# IndAlarmSe0.net
KiCad netlist of a schematic drawn in Altium Designer
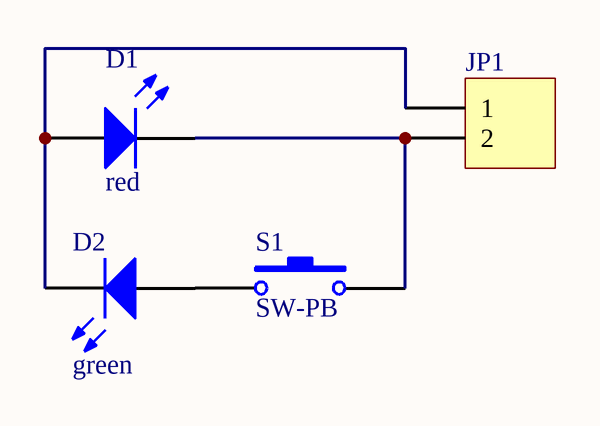
[diagram p0: IndAlarmSe0.SchDoc]

(export (version "E")
  (design (tool "Eeschema 10.0.6"))
  (components
    (comp (ref "D1")
      (value "red")
      (footprint "myLIB:led3mm")
      (description "Typical BLUE SiC LED")
      (fields (field (name "PUBLISHER") "Altium Limited"))
      (libsource (lib "Miscellaneous Devices") (part "LED3"))
    )
    (comp (ref "D2")
      (value "green")
      (footprint "myLIB:LED3MM")
      (description "Typical BLUE SiC LED")
      (fields (field (name "PUBLISHER") "Altium Limited"))
      (libsource (lib "Miscellaneous Devices") (part "LED3"))
    )
    (comp (ref "JP1")
      (value "~")
      (footprint "HDR1X2")
      (description "Header, 2-Pin")
      (fields (field (name "PUBLISHER") "Altium Limited"))
      (libsource (lib "Miscellaneous Connectors") (part "Header 2"))
    )
    (comp (ref "S1")
      (value "SW-PB")
      (footprint "myLIB:SPPB512300")
      (description "Switch")
      (fields (field (name "PUBLISHER") "Altium Limited"))
      (libsource (lib "Miscellaneous Devices") (part "SW-PB"))
    )
  )
  (nets
    (net (code "1") (name "Net-(D1-A)") (class "Default")
      (node (ref "D1") (pin "1") (pinfunction "A_1") (pintype "passive"))
      (node (ref "D2") (pin "2") (pinfunction "K_2") (pintype "passive"))
      (node (ref "JP1") (pin "1") (pinfunction "1_1") (pintype "passive"))
    )
    (net (code "2") (name "Net-(D1-K)") (class "Default")
      (node (ref "D1") (pin "2") (pinfunction "K_2") (pintype "passive"))
      (node (ref "JP1") (pin "2") (pinfunction "2_2") (pintype "passive"))
      (node (ref "S1") (pin "2") (pinfunction "2_2") (pintype "passive"))
    )
    (net (code "3") (name "Net-(D2-A)") (class "Default")
      (node (ref "D2") (pin "1") (pinfunction "A_1") (pintype "passive"))
      (node (ref "S1") (pin "1") (pinfunction "1_1") (pintype "passive"))
    )
  )
)
